# FiltrosRF_R00.net
KiCad netlist of a schematic drawn in Altium Designer
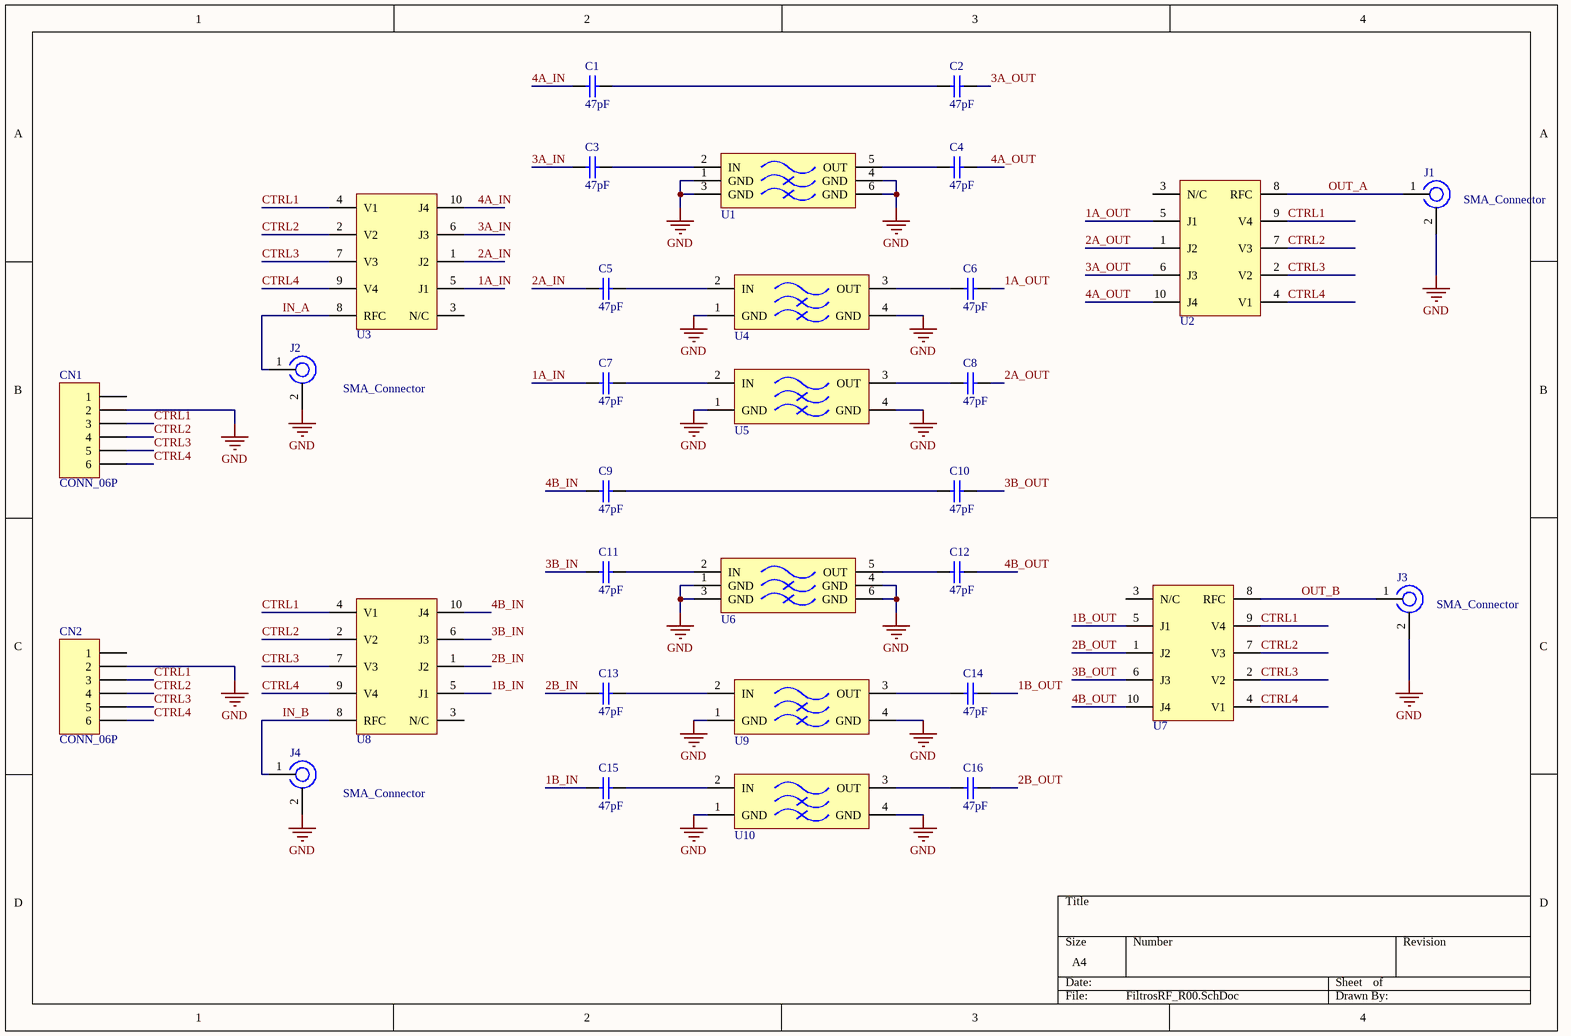
[diagram p0: FiltrosRF_R00.SchDoc]

(export (version "E")
  (design (tool "Eeschema 10.0.6"))
  (components
    (comp (ref "C1")
      (value "47pF")
      (footprint "C_0603")
      (description "Capacitor")
      (libsource (lib "Simulation Generic Components") (part "Capacitor"))
    )
    (comp (ref "C2")
      (value "47pF")
      (footprint "C_0603")
      (description "Capacitor")
      (libsource (lib "Simulation Generic Components") (part "Capacitor"))
    )
    (comp (ref "C3")
      (value "47pF")
      (footprint "C_0603")
      (description "Capacitor")
      (libsource (lib "Simulation Generic Components") (part "Capacitor"))
    )
    (comp (ref "C4")
      (value "47pF")
      (footprint "C_0603")
      (description "Capacitor")
      (libsource (lib "Simulation Generic Components") (part "Capacitor"))
    )
    (comp (ref "C5")
      (value "47pF")
      (footprint "C_0603")
      (description "Capacitor")
      (libsource (lib "Simulation Generic Components") (part "Capacitor"))
    )
    (comp (ref "C6")
      (value "47pF")
      (footprint "C_0603")
      (description "Capacitor")
      (libsource (lib "Simulation Generic Components") (part "Capacitor"))
    )
    (comp (ref "C7")
      (value "47pF")
      (footprint "C_0603")
      (description "Capacitor")
      (libsource (lib "Simulation Generic Components") (part "Capacitor"))
    )
    (comp (ref "C8")
      (value "47pF")
      (footprint "C_0603")
      (description "Capacitor")
      (libsource (lib "Simulation Generic Components") (part "Capacitor"))
    )
    (comp (ref "C9")
      (value "47pF")
      (footprint "C_0603")
      (description "Capacitor")
      (libsource (lib "Simulation Generic Components") (part "Capacitor"))
    )
    (comp (ref "C10")
      (value "47pF")
      (footprint "C_0603")
      (description "Capacitor")
      (libsource (lib "Simulation Generic Components") (part "Capacitor"))
    )
    (comp (ref "C11")
      (value "47pF")
      (footprint "C_0603")
      (description "Capacitor")
      (libsource (lib "Simulation Generic Components") (part "Capacitor"))
    )
    (comp (ref "C12")
      (value "47pF")
      (footprint "C_0603")
      (description "Capacitor")
      (libsource (lib "Simulation Generic Components") (part "Capacitor"))
    )
    (comp (ref "C13")
      (value "47pF")
      (footprint "C_0603")
      (description "Capacitor")
      (libsource (lib "Simulation Generic Components") (part "Capacitor"))
    )
    (comp (ref "C14")
      (value "47pF")
      (footprint "C_0603")
      (description "Capacitor")
      (libsource (lib "Simulation Generic Components") (part "Capacitor"))
    )
    (comp (ref "C15")
      (value "47pF")
      (footprint "C_0603")
      (description "Capacitor")
      (libsource (lib "Simulation Generic Components") (part "Capacitor"))
    )
    (comp (ref "C16")
      (value "47pF")
      (footprint "C_0603")
      (description "Capacitor")
      (libsource (lib "Simulation Generic Components") (part "Capacitor"))
    )
    (comp (ref "CN1")
      (value "CONN_06P")
      (footprint "Header_M_1x6_0.1\"")
      (description "Connector Generic 4 Vias")
      (libsource (lib "SchLib_PocketAnalyzer") (part "CONN_06P"))
    )
    (comp (ref "CN2")
      (value "CONN_06P")
      (footprint "Header_M_1x6_0.1\"")
      (description "Connector Generic 4 Vias")
      (libsource (lib "SchLib_PocketAnalyzer") (part "CONN_06P"))
    )
    (comp (ref "J1")
      (value "SMA_Connector")
      (footprint "SMA_Connector")
      (description "Connector SMA")
      (libsource (lib "SchLib_PocketAnalyzer") (part "SMA_Connector"))
    )
    (comp (ref "J2")
      (value "SMA_Connector")
      (footprint "SMA_Connector")
      (description "Connector SMA")
      (libsource (lib "SchLib_PocketAnalyzer") (part "SMA_Connector"))
    )
    (comp (ref "J3")
      (value "SMA_Connector")
      (footprint "SMA_Connector")
      (description "Connector SMA")
      (libsource (lib "SchLib_PocketAnalyzer") (part "SMA_Connector"))
    )
    (comp (ref "J4")
      (value "SMA_Connector")
      (footprint "SMA_Connector")
      (description "Connector SMA")
      (libsource (lib "SchLib_PocketAnalyzer") (part "SMA_Connector"))
    )
    (comp (ref "U1")
      (value "3550LP14A0300001T")
      (footprint "Low Pass Filter 0603 6 Pins")
      (description "RF FILTER LOW PASS  0603")
      (libsource (lib "FiltrosRF") (part "3550LP14A0300001T"))
    )
    (comp (ref "U2")
      (value "SKY13322-375LF")
      (description "RF Switch IC General Purpose SP4T 6 GHz 50Ohm 10-MLPD (3x2)")
      (libsource (lib "FiltrosRF") (part "SKY13322-375LF"))
    )
    (comp (ref "U3")
      (value "SKY13322-375LF")
      (description "RF Switch IC General Purpose SP4T 6 GHz 50Ohm 10-MLPD (3x2)")
      (libsource (lib "") (part "SKY13322-375LF_1"))
    )
    (comp (ref "U4")
      (value "LP0603A-XXXX-ANTR")
      (footprint "Low Pass Filter 0603 4 Pins")
      (description "RF FILTER 0603")
      (libsource (lib "FiltrosRF") (part "LP0603A-XXXX-ANTR"))
    )
    (comp (ref "U5")
      (value "LP0603A-XXXX-ANTR")
      (footprint "Low Pass Filter 0603 4 Pins")
      (description "RF FILTER 0603")
      (libsource (lib "FiltrosRF") (part "LP0603A-XXXX-ANTR"))
    )
    (comp (ref "U6")
      (value "3550LP14A0300001T")
      (footprint "Low Pass Filter 0603 6 Pins")
      (description "RF FILTER LOW PASS  0603")
      (libsource (lib "FiltrosRF") (part "3550LP14A0300001T"))
    )
    (comp (ref "U7")
      (value "SKY13322-375LF")
      (description "RF Switch IC General Purpose SP4T 6 GHz 50Ohm 10-MLPD (3x2)")
      (libsource (lib "FiltrosRF") (part "SKY13322-375LF"))
    )
    (comp (ref "U8")
      (value "SKY13322-375LF")
      (description "RF Switch IC General Purpose SP4T 6 GHz 50Ohm 10-MLPD (3x2)")
      (libsource (lib "") (part "SKY13322-375LF_1"))
    )
    (comp (ref "U9")
      (value "LP0603A-XXXX-ANTR")
      (footprint "Low Pass Filter 0603 4 Pins")
      (description "RF FILTER 0603")
      (libsource (lib "FiltrosRF") (part "LP0603A-XXXX-ANTR"))
    )
    (comp (ref "U10")
      (value "LP0603A-XXXX-ANTR")
      (footprint "Low Pass Filter 0603 4 Pins")
      (description "RF FILTER 0603")
      (libsource (lib "FiltrosRF") (part "LP0603A-XXXX-ANTR"))
    )
  )
  (nets
    (net (code "1") (name "/1A_IN") (class "Default")
      (node (ref "C7") (pin "1") (pinfunction "1_1") (pintype "passive"))
      (node (ref "U3") (pin "5") (pinfunction "J1_5") (pintype "passive"))
    )
    (net (code "2") (name "/1A_OUT") (class "Default")
      (node (ref "C6") (pin "2") (pinfunction "2_2") (pintype "passive"))
      (node (ref "U2") (pin "5") (pinfunction "J1_5") (pintype "passive"))
    )
    (net (code "3") (name "/1B_IN") (class "Default")
      (node (ref "C15") (pin "1") (pinfunction "1_1") (pintype "passive"))
      (node (ref "U8") (pin "5") (pinfunction "J1_5") (pintype "passive"))
    )
    (net (code "4") (name "/1B_OUT") (class "Default")
      (node (ref "C14") (pin "2") (pinfunction "2_2") (pintype "passive"))
      (node (ref "U7") (pin "5") (pinfunction "J1_5") (pintype "passive"))
    )
    (net (code "5") (name "/2A_IN") (class "Default")
      (node (ref "C5") (pin "1") (pinfunction "1_1") (pintype "passive"))
      (node (ref "U3") (pin "1") (pinfunction "J2_1") (pintype "passive"))
    )
    (net (code "6") (name "/2A_OUT") (class "Default")
      (node (ref "C8") (pin "2") (pinfunction "2_2") (pintype "passive"))
      (node (ref "U2") (pin "1") (pinfunction "J2_1") (pintype "passive"))
    )
    (net (code "7") (name "/2B_IN") (class "Default")
      (node (ref "C13") (pin "1") (pinfunction "1_1") (pintype "passive"))
      (node (ref "U8") (pin "1") (pinfunction "J2_1") (pintype "passive"))
    )
    (net (code "8") (name "/2B_OUT") (class "Default")
      (node (ref "C16") (pin "2") (pinfunction "2_2") (pintype "passive"))
      (node (ref "U7") (pin "1") (pinfunction "J2_1") (pintype "passive"))
    )
    (net (code "9") (name "/3A_IN") (class "Default")
      (node (ref "C3") (pin "1") (pinfunction "1_1") (pintype "passive"))
      (node (ref "U3") (pin "6") (pinfunction "J3_6") (pintype "passive"))
    )
    (net (code "10") (name "/3A_OUT") (class "Default")
      (node (ref "C2") (pin "2") (pinfunction "2_2") (pintype "passive"))
      (node (ref "U2") (pin "6") (pinfunction "J3_6") (pintype "passive"))
    )
    (net (code "11") (name "/3B_IN") (class "Default")
      (node (ref "C11") (pin "1") (pinfunction "1_1") (pintype "passive"))
      (node (ref "U8") (pin "6") (pinfunction "J3_6") (pintype "passive"))
    )
    (net (code "12") (name "/3B_OUT") (class "Default")
      (node (ref "C10") (pin "2") (pinfunction "2_2") (pintype "passive"))
      (node (ref "U7") (pin "6") (pinfunction "J3_6") (pintype "passive"))
    )
    (net (code "13") (name "/4A_IN") (class "Default")
      (node (ref "C1") (pin "1") (pinfunction "1_1") (pintype "passive"))
      (node (ref "U3") (pin "10") (pinfunction "J4_10") (pintype "passive"))
    )
    (net (code "14") (name "/4A_OUT") (class "Default")
      (node (ref "C4") (pin "2") (pinfunction "2_2") (pintype "passive"))
      (node (ref "U2") (pin "10") (pinfunction "J4_10") (pintype "passive"))
    )
    (net (code "15") (name "/4B_IN") (class "Default")
      (node (ref "C9") (pin "1") (pinfunction "1_1") (pintype "passive"))
      (node (ref "U8") (pin "10") (pinfunction "J4_10") (pintype "passive"))
    )
    (net (code "16") (name "/4B_OUT") (class "Default")
      (node (ref "C12") (pin "2") (pinfunction "2_2") (pintype "passive"))
      (node (ref "U7") (pin "10") (pinfunction "J4_10") (pintype "passive"))
    )
    (net (code "17") (name "/CTRL1") (class "Default")
      (node (ref "CN1") (pin "3") (pinfunction "3_3") (pintype "passive"))
      (node (ref "CN2") (pin "3") (pinfunction "3_3") (pintype "passive"))
      (node (ref "U2") (pin "9") (pinfunction "V4_9") (pintype "passive"))
      (node (ref "U3") (pin "4") (pinfunction "V1_4") (pintype "passive"))
      (node (ref "U7") (pin "9") (pinfunction "V4_9") (pintype "passive"))
      (node (ref "U8") (pin "4") (pinfunction "V1_4") (pintype "passive"))
    )
    (net (code "18") (name "/CTRL2") (class "Default")
      (node (ref "CN1") (pin "4") (pinfunction "4_4") (pintype "passive"))
      (node (ref "CN2") (pin "4") (pinfunction "4_4") (pintype "passive"))
      (node (ref "U2") (pin "7") (pinfunction "V3_7") (pintype "passive"))
      (node (ref "U3") (pin "2") (pinfunction "V2_2") (pintype "passive"))
      (node (ref "U7") (pin "7") (pinfunction "V3_7") (pintype "passive"))
      (node (ref "U8") (pin "2") (pinfunction "V2_2") (pintype "passive"))
    )
    (net (code "19") (name "/CTRL3") (class "Default")
      (node (ref "CN1") (pin "5") (pinfunction "5_5") (pintype "passive"))
      (node (ref "CN2") (pin "5") (pinfunction "5_5") (pintype "passive"))
      (node (ref "U2") (pin "2") (pinfunction "V2_2") (pintype "passive"))
      (node (ref "U3") (pin "7") (pinfunction "V3_7") (pintype "passive"))
      (node (ref "U7") (pin "2") (pinfunction "V2_2") (pintype "passive"))
      (node (ref "U8") (pin "7") (pinfunction "V3_7") (pintype "passive"))
    )
    (net (code "20") (name "/CTRL4") (class "Default")
      (node (ref "CN1") (pin "6") (pinfunction "6_6") (pintype "passive"))
      (node (ref "CN2") (pin "6") (pinfunction "6_6") (pintype "passive"))
      (node (ref "U2") (pin "4") (pinfunction "V1_4") (pintype "passive"))
      (node (ref "U3") (pin "9") (pinfunction "V4_9") (pintype "passive"))
      (node (ref "U7") (pin "4") (pinfunction "V1_4") (pintype "passive"))
      (node (ref "U8") (pin "9") (pinfunction "V4_9") (pintype "passive"))
    )
    (net (code "21") (name "/IN_A") (class "Default")
      (node (ref "J2") (pin "1") (pinfunction "1_1") (pintype "passive"))
      (node (ref "U3") (pin "8") (pinfunction "RFC_8") (pintype "passive"))
    )
    (net (code "22") (name "/IN_B") (class "Default")
      (node (ref "J4") (pin "1") (pinfunction "1_1") (pintype "passive"))
      (node (ref "U8") (pin "8") (pinfunction "RFC_8") (pintype "passive"))
    )
    (net (code "23") (name "/OUT_A") (class "Default")
      (node (ref "J1") (pin "1") (pinfunction "1_1") (pintype "passive"))
      (node (ref "U2") (pin "8") (pinfunction "RFC_8") (pintype "passive"))
    )
    (net (code "24") (name "/OUT_B") (class "Default")
      (node (ref "J3") (pin "1") (pinfunction "1_1") (pintype "passive"))
      (node (ref "U7") (pin "8") (pinfunction "RFC_8") (pintype "passive"))
    )
    (net (code "25") (name "GND") (class "Default")
      (node (ref "CN1") (pin "2") (pinfunction "2_2") (pintype "passive"))
      (node (ref "CN2") (pin "2") (pinfunction "2_2") (pintype "passive"))
      (node (ref "J1") (pin "2") (pinfunction "2_2") (pintype "passive"))
      (node (ref "J2") (pin "2") (pinfunction "2_2") (pintype "passive"))
      (node (ref "J3") (pin "2") (pinfunction "2_2") (pintype "passive"))
      (node (ref "J4") (pin "2") (pinfunction "2_2") (pintype "passive"))
      (node (ref "U1") (pin "1") (pinfunction "GND_1") (pintype "passive"))
      (node (ref "U1") (pin "3") (pinfunction "GND_3") (pintype "passive"))
      (node (ref "U1") (pin "4") (pinfunction "GND_4") (pintype "passive"))
      (node (ref "U1") (pin "6") (pinfunction "GND_6") (pintype "passive"))
      (node (ref "U10") (pin "1") (pinfunction "GND_1") (pintype "passive"))
      (node (ref "U10") (pin "4") (pinfunction "GND_4") (pintype "passive"))
      (node (ref "U4") (pin "1") (pinfunction "GND_1") (pintype "passive"))
      (node (ref "U4") (pin "4") (pinfunction "GND_4") (pintype "passive"))
      (node (ref "U5") (pin "1") (pinfunction "GND_1") (pintype "passive"))
      (node (ref "U5") (pin "4") (pinfunction "GND_4") (pintype "passive"))
      (node (ref "U6") (pin "1") (pinfunction "GND_1") (pintype "passive"))
      (node (ref "U6") (pin "3") (pinfunction "GND_3") (pintype "passive"))
      (node (ref "U6") (pin "4") (pinfunction "GND_4") (pintype "passive"))
      (node (ref "U6") (pin "6") (pinfunction "GND_6") (pintype "passive"))
      (node (ref "U9") (pin "1") (pinfunction "GND_1") (pintype "passive"))
      (node (ref "U9") (pin "4") (pinfunction "GND_4") (pintype "passive"))
    )
    (net (code "26") (name "Net-(C1-Pad2)") (class "Default")
      (node (ref "C1") (pin "2") (pinfunction "2_2") (pintype "passive"))
      (node (ref "C2") (pin "1") (pinfunction "1_1") (pintype "passive"))
    )
    (net (code "27") (name "Net-(C10-Pad1)") (class "Default")
      (node (ref "C10") (pin "1") (pinfunction "1_1") (pintype "passive"))
      (node (ref "C9") (pin "2") (pinfunction "2_2") (pintype "passive"))
    )
    (net (code "28") (name "Net-(U1-IN)") (class "Default")
      (node (ref "C3") (pin "2") (pinfunction "2_2") (pintype "passive"))
      (node (ref "U1") (pin "2") (pinfunction "IN_2") (pintype "passive"))
    )
    (net (code "29") (name "Net-(U1-OUT)") (class "Default")
      (node (ref "C4") (pin "1") (pinfunction "1_1") (pintype "passive"))
      (node (ref "U1") (pin "5") (pinfunction "OUT_5") (pintype "passive"))
    )
    (net (code "30") (name "Net-(U4-IN)") (class "Default")
      (node (ref "C5") (pin "2") (pinfunction "2_2") (pintype "passive"))
      (node (ref "U4") (pin "2") (pinfunction "IN_2") (pintype "passive"))
    )
    (net (code "31") (name "Net-(U4-OUT)") (class "Default")
      (node (ref "C6") (pin "1") (pinfunction "1_1") (pintype "passive"))
      (node (ref "U4") (pin "3") (pinfunction "OUT_3") (pintype "passive"))
    )
    (net (code "32") (name "Net-(U5-IN)") (class "Default")
      (node (ref "C7") (pin "2") (pinfunction "2_2") (pintype "passive"))
      (node (ref "U5") (pin "2") (pinfunction "IN_2") (pintype "passive"))
    )
    (net (code "33") (name "Net-(U5-OUT)") (class "Default")
      (node (ref "C8") (pin "1") (pinfunction "1_1") (pintype "passive"))
      (node (ref "U5") (pin "3") (pinfunction "OUT_3") (pintype "passive"))
    )
    (net (code "34") (name "Net-(U6-IN)") (class "Default")
      (node (ref "C11") (pin "2") (pinfunction "2_2") (pintype "passive"))
      (node (ref "U6") (pin "2") (pinfunction "IN_2") (pintype "passive"))
    )
    (net (code "35") (name "Net-(U6-OUT)") (class "Default")
      (node (ref "C12") (pin "1") (pinfunction "1_1") (pintype "passive"))
      (node (ref "U6") (pin "5") (pinfunction "OUT_5") (pintype "passive"))
    )
    (net (code "36") (name "Net-(U9-IN)") (class "Default")
      (node (ref "C13") (pin "2") (pinfunction "2_2") (pintype "passive"))
      (node (ref "U9") (pin "2") (pinfunction "IN_2") (pintype "passive"))
    )
    (net (code "37") (name "Net-(U9-OUT)") (class "Default")
      (node (ref "C14") (pin "1") (pinfunction "1_1") (pintype "passive"))
      (node (ref "U9") (pin "3") (pinfunction "OUT_3") (pintype "passive"))
    )
    (net (code "38") (name "Net-(U10-IN)") (class "Default")
      (node (ref "C15") (pin "2") (pinfunction "2_2") (pintype "passive"))
      (node (ref "U10") (pin "2") (pinfunction "IN_2") (pintype "passive"))
    )
    (net (code "39") (name "Net-(U10-OUT)") (class "Default")
      (node (ref "C16") (pin "1") (pinfunction "1_1") (pintype "passive"))
      (node (ref "U10") (pin "3") (pinfunction "OUT_3") (pintype "passive"))
    )
    (net (code "40") (name "unconnected-(CN1-Pad1)") (class "Default")
      (node (ref "CN1") (pin "1") (pinfunction "1_1") (pintype "passive"))
    )
    (net (code "41") (name "unconnected-(CN2-Pad1)") (class "Default")
      (node (ref "CN2") (pin "1") (pinfunction "1_1") (pintype "passive"))
    )
    (net (code "42") (name "unconnected-(U2-N{slash}C-Pad3)") (class "Default")
      (node (ref "U2") (pin "3") (pinfunction "N/C_3") (pintype "passive"))
    )
    (net (code "43") (name "unconnected-(U3-N{slash}C-Pad3)") (class "Default")
      (node (ref "U3") (pin "3") (pinfunction "N/C_3") (pintype "passive"))
    )
    (net (code "44") (name "unconnected-(U7-N{slash}C-Pad3)") (class "Default")
      (node (ref "U7") (pin "3") (pinfunction "N/C_3") (pintype "passive"))
    )
    (net (code "45") (name "unconnected-(U8-N{slash}C-Pad3)") (class "Default")
      (node (ref "U8") (pin "3") (pinfunction "N/C_3") (pintype "passive"))
    )
  )
)
